# Hierarchical_schematics_design.net
KiCad netlist of a schematic drawn in Altium Designer
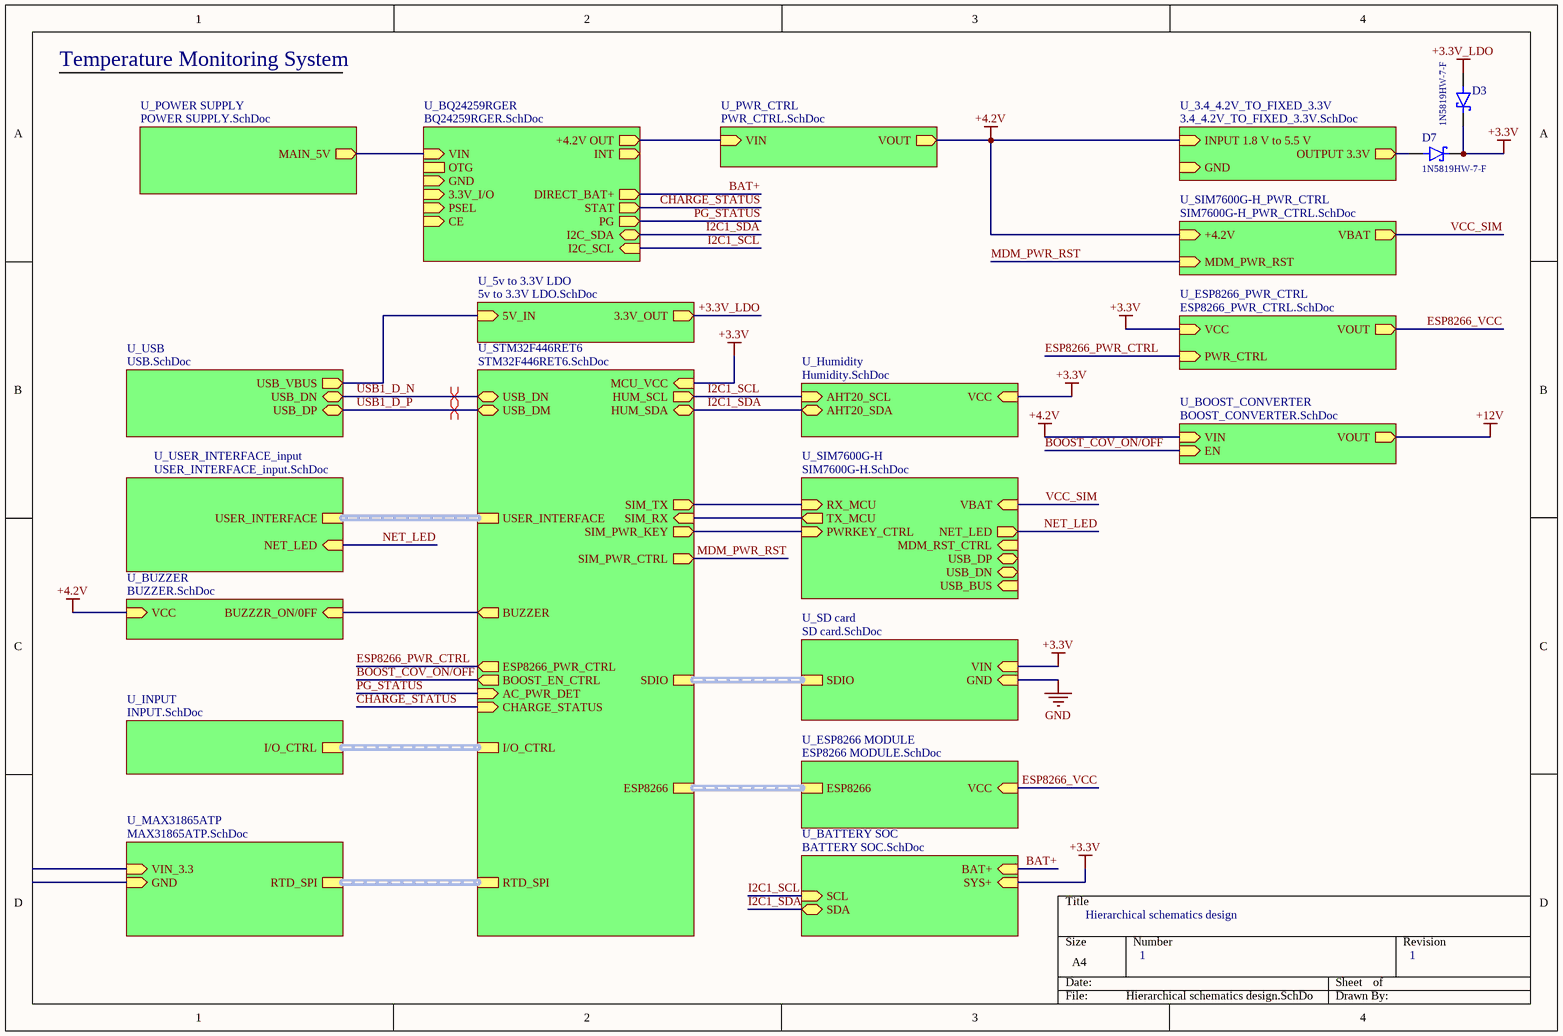
[diagram p0: Hierarchical schematics design.SchDoc]

(export (version "E")
  (design (tool "Eeschema 10.0.6"))
  (components
    (comp (ref "D3")
      (value "1N5819HW-7-F")
      (footprint "SOD3715X145N")
      (description "Diode Schottky 40 V 1A Surface Mount SOD-123")
      (fields (field (name "MF") "Diodes Inc."))
      (libsource (lib "RCL") (part "1N5819HW-7-F"))
    )
    (comp (ref "D7")
      (value "1N5819HW-7-F")
      (footprint "SOD3715X145N")
      (description "Diode Schottky 40 V 1A Surface Mount SOD-123")
      (fields (field (name "MF") "Diodes Inc."))
      (libsource (lib "RCL") (part "1N5819HW-7-F"))
    )
  )
  (nets
    (net (code "1") (name "+3.3V") (class "Default")
      (node (ref "D3") (pin "C") (pinfunction "K_C") (pintype "passive"))
      (node (ref "D7") (pin "C") (pinfunction "K_C") (pintype "passive"))
    )
    (net (code "2") (name "+3.3V_LDO") (class "Default")
      (node (ref "D3") (pin "A") (pinfunction "A_A") (pintype "passive"))
    )
    (net (code "27") (name "/OUTPUT 3.3V") (class "Default")
      (node (ref "D7") (pin "A") (pinfunction "A_A") (pintype "passive"))
    )
  )
)
